# ver3.net
KiCad netlist of a schematic drawn in EAGLE
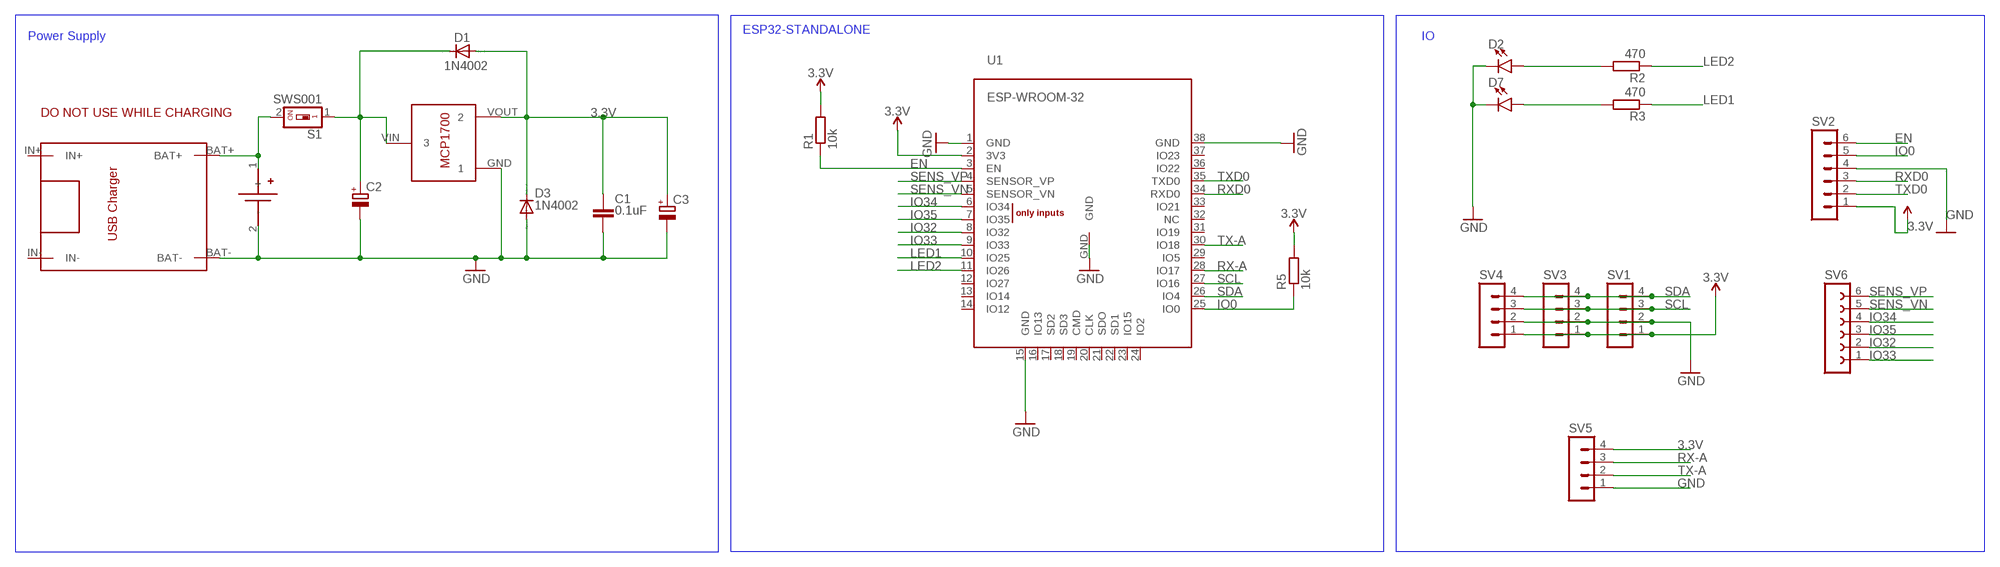
[diagram p0: schematic, sheet 1]

(export (version "E")
  (design (tool "Eeschema 10.0.6"))
  (components
    (comp (ref "C1")
      (value "0.1uF")
      (footprint "eagle-import:C075-052X106")
      (libsource (lib "eagle-import") (part "C-EU075-052X106"))
    )
    (comp (ref "C2")
      (value "CPOL-EU085CS-1AR")
      (footprint "eagle-import:085CS_1AR")
      (libsource (lib "eagle-import") (part "CPOL-EU085CS-1AR"))
    )
    (comp (ref "C3")
      (value "CPOL-EU085CS-1AR")
      (footprint "eagle-import:085CS_1AR")
      (libsource (lib "eagle-import") (part "CPOL-EU085CS-1AR"))
    )
    (comp (ref "D1")
      (value "1N4002")
      (footprint "eagle-import:DO41-10")
      (libsource (lib "eagle-import") (part "1N4004"))
    )
    (comp (ref "D2")
      (value "LED-3MM-NO_SILK")
      (footprint "eagle-import:LED_3MM-NS")
      (libsource (lib "eagle-import") (part "LED-3MM-NO_SILK"))
    )
    (comp (ref "D3")
      (value "1N4002")
      (footprint "eagle-import:DO41-10")
      (libsource (lib "eagle-import") (part "1N4004"))
    )
    (comp (ref "D7")
      (value "LED-3MM-NO_SILK")
      (footprint "eagle-import:LED_3MM-NS")
      (libsource (lib "eagle-import") (part "LED-3MM-NO_SILK"))
    )
    (comp (ref "R1")
      (value "10k")
      (footprint "eagle-import:R0603")
      (libsource (lib "eagle-import") (part "R-EU_R0603"))
    )
    (comp (ref "R2")
      (value "470")
      (footprint "eagle-import:R0603")
      (libsource (lib "eagle-import") (part "R-EU_R0603"))
    )
    (comp (ref "R3")
      (value "470")
      (footprint "eagle-import:R0603")
      (libsource (lib "eagle-import") (part "R-EU_R0603"))
    )
    (comp (ref "R5")
      (value "10k")
      (footprint "eagle-import:R0603")
      (libsource (lib "eagle-import") (part "R-EU_R0603"))
    )
    (comp (ref "S1")
      (value "SWS001")
      (footprint "eagle-import:SMS-001")
      (libsource (lib "eagle-import") (part "SWS001"))
    )
    (comp (ref "SV1")
      (value "MA04-1")
      (footprint "eagle-import:MA04-1")
      (libsource (lib "eagle-import") (part "MA04-1"))
    )
    (comp (ref "SV2")
      (value "MA06-1")
      (footprint "eagle-import:MA06-1")
      (libsource (lib "eagle-import") (part "MA06-1"))
    )
    (comp (ref "SV3")
      (value "MA04-1")
      (footprint "eagle-import:MA04-1")
      (libsource (lib "eagle-import") (part "MA04-1"))
    )
    (comp (ref "SV4")
      (value "MA04-1")
      (footprint "eagle-import:MA04-1")
      (libsource (lib "eagle-import") (part "MA04-1"))
    )
    (comp (ref "SV5")
      (value "MA04-1")
      (footprint "eagle-import:MA04-1")
      (libsource (lib "eagle-import") (part "MA04-1"))
    )
    (comp (ref "SV6")
      (value "FE06-1")
      (footprint "eagle-import:FE06")
      (libsource (lib "eagle-import") (part "FE06-1"))
    )
    (comp (ref "U$1")
      (value "BLOSSOM-BLM-18650-1PCS")
      (footprint "eagle-import:BLOSSOM-BLM-18650-1PCS")
      (libsource (lib "eagle-import") (part "BLOSSOM-BLM-18650-1PCS"))
    )
    (comp (ref "U$2")
      (value "TP4056")
      (footprint "eagle-import:TP4056")
      (libsource (lib "eagle-import") (part "TP4056"))
    )
    (comp (ref "U$3")
      (value "MCP1700T-3302E/TT")
      (footprint "eagle-import:MCP1700T-3302E_TT")
      (libsource (lib "eagle-import") (part "MCP1700T-3302E/TT"))
    )
    (comp (ref "U1")
      (value "ESP-WROOM-32")
      (footprint "eagle-import:ESP-WROOM-32")
      (libsource (lib "eagle-import") (part "ESP-WROOM-32"))
    )
  )
  (nets
    (net (code "1") (name "/EN") (class "Default")
      (node (ref "R1") (pin "1") (pinfunction "1_1") (pintype "passive"))
      (node (ref "SV2") (pin "6") (pinfunction "6_6") (pintype "passive"))
      (node (ref "U1") (pin "3") (pinfunction "EN_3") (pintype "bidirectional"))
    )
    (net (code "2") (name "/IO0") (class "Default")
      (node (ref "R5") (pin "1") (pinfunction "1_1") (pintype "passive"))
      (node (ref "SV2") (pin "5") (pinfunction "5_5") (pintype "passive"))
      (node (ref "U1") (pin "25") (pinfunction "IO0_25") (pintype "bidirectional"))
    )
    (net (code "3") (name "/IO32") (class "Default")
      (node (ref "SV6") (pin "2") (pinfunction "2_2") (pintype "passive"))
      (node (ref "U1") (pin "8") (pinfunction "IO32_8") (pintype "bidirectional"))
    )
    (net (code "4") (name "/IO33") (class "Default")
      (node (ref "SV6") (pin "1") (pinfunction "1_1") (pintype "passive"))
      (node (ref "U1") (pin "9") (pinfunction "IO33_9") (pintype "bidirectional"))
    )
    (net (code "5") (name "/IO34") (class "Default")
      (node (ref "SV6") (pin "4") (pinfunction "4_4") (pintype "passive"))
      (node (ref "U1") (pin "6") (pinfunction "IO34_6") (pintype "input"))
    )
    (net (code "6") (name "/IO35") (class "Default")
      (node (ref "SV6") (pin "3") (pinfunction "3_3") (pintype "passive"))
      (node (ref "U1") (pin "7") (pinfunction "IO35_7") (pintype "input"))
    )
    (net (code "7") (name "/LED1") (class "Default")
      (node (ref "R3") (pin "1") (pinfunction "1_1") (pintype "passive"))
      (node (ref "U1") (pin "10") (pinfunction "IO25_10") (pintype "bidirectional"))
    )
    (net (code "8") (name "/LED2") (class "Default")
      (node (ref "R2") (pin "1") (pinfunction "1_1") (pintype "passive"))
      (node (ref "U1") (pin "11") (pinfunction "IO26_11") (pintype "bidirectional"))
    )
    (net (code "9") (name "/RX-A") (class "Default")
      (node (ref "SV5") (pin "3") (pinfunction "3_3") (pintype "passive"))
      (node (ref "U1") (pin "28") (pinfunction "IO17_28") (pintype "bidirectional"))
    )
    (net (code "10") (name "/RXD0") (class "Default")
      (node (ref "SV2") (pin "3") (pinfunction "3_3") (pintype "passive"))
      (node (ref "U1") (pin "34") (pinfunction "RXD0_34") (pintype "bidirectional"))
    )
    (net (code "11") (name "/SCL") (class "Default")
      (node (ref "SV1") (pin "3") (pinfunction "3_3") (pintype "passive"))
      (node (ref "SV3") (pin "3") (pinfunction "3_3") (pintype "passive"))
      (node (ref "SV4") (pin "3") (pinfunction "3_3") (pintype "passive"))
      (node (ref "U1") (pin "27") (pinfunction "IO16_27") (pintype "bidirectional"))
    )
    (net (code "12") (name "/SDA") (class "Default")
      (node (ref "SV1") (pin "4") (pinfunction "4_4") (pintype "passive"))
      (node (ref "SV3") (pin "4") (pinfunction "4_4") (pintype "passive"))
      (node (ref "SV4") (pin "4") (pinfunction "4_4") (pintype "passive"))
      (node (ref "U1") (pin "26") (pinfunction "IO4_26") (pintype "bidirectional"))
    )
    (net (code "13") (name "/SENS_VN") (class "Default")
      (node (ref "SV6") (pin "5") (pinfunction "5_5") (pintype "passive"))
      (node (ref "U1") (pin "5") (pinfunction "SENSOR_VN_5") (pintype "input"))
    )
    (net (code "14") (name "/SENS_VP") (class "Default")
      (node (ref "SV6") (pin "6") (pinfunction "6_6") (pintype "passive"))
      (node (ref "U1") (pin "4") (pinfunction "SENSOR_VP_4") (pintype "input"))
    )
    (net (code "15") (name "/TX-A") (class "Default")
      (node (ref "SV5") (pin "2") (pinfunction "2_2") (pintype "passive"))
      (node (ref "U1") (pin "30") (pinfunction "IO18_30") (pintype "bidirectional"))
    )
    (net (code "16") (name "/TXD0") (class "Default")
      (node (ref "SV2") (pin "2") (pinfunction "2_2") (pintype "passive"))
      (node (ref "U1") (pin "35") (pinfunction "TXD0_35") (pintype "bidirectional"))
    )
    (net (code "17") (name "3.3V") (class "Default")
      (node (ref "C1") (pin "1") (pinfunction "1_1") (pintype "passive"))
      (node (ref "C3") (pin "+") (pinfunction "+_+") (pintype "passive"))
      (node (ref "D1") (pin "A") (pinfunction "A_A") (pintype "passive"))
      (node (ref "D3") (pin "C") (pinfunction "C_C") (pintype "passive"))
      (node (ref "R1") (pin "2") (pinfunction "2_2") (pintype "passive"))
      (node (ref "R5") (pin "2") (pinfunction "2_2") (pintype "passive"))
      (node (ref "SV1") (pin "1") (pinfunction "1_1") (pintype "passive"))
      (node (ref "SV2") (pin "1") (pinfunction "1_1") (pintype "passive"))
      (node (ref "SV3") (pin "1") (pinfunction "1_1") (pintype "passive"))
      (node (ref "SV4") (pin "1") (pinfunction "1_1") (pintype "passive"))
      (node (ref "SV5") (pin "4") (pinfunction "4_4") (pintype "passive"))
      (node (ref "U$3") (pin "VOUT") (pinfunction "2_VOUT") (pintype "bidirectional"))
      (node (ref "U1") (pin "2") (pinfunction "3V3_2") (pintype "bidirectional"))
    )
    (net (code "18") (name "GND") (class "Default")
      (node (ref "C1") (pin "2") (pinfunction "2_2") (pintype "passive"))
      (node (ref "C2") (pin "-") (pinfunction "-_-") (pintype "passive"))
      (node (ref "C3") (pin "-") (pinfunction "-_-") (pintype "passive"))
      (node (ref "D2") (pin "K") (pinfunction "C_K") (pintype "passive"))
      (node (ref "D3") (pin "A") (pinfunction "A_A") (pintype "passive"))
      (node (ref "D7") (pin "K") (pinfunction "C_K") (pintype "passive"))
      (node (ref "SV1") (pin "2") (pinfunction "2_2") (pintype "passive"))
      (node (ref "SV2") (pin "4") (pinfunction "4_4") (pintype "passive"))
      (node (ref "SV3") (pin "2") (pinfunction "2_2") (pintype "passive"))
      (node (ref "SV4") (pin "2") (pinfunction "2_2") (pintype "passive"))
      (node (ref "SV5") (pin "1") (pinfunction "1_1") (pintype "passive"))
      (node (ref "U$1") (pin "2") (pinfunction "-_2") (pintype "bidirectional"))
      (node (ref "U$2") (pin "BAT-") (pinfunction "BAT-_BAT-") (pintype "bidirectional"))
      (node (ref "U$3") (pin "GND") (pinfunction "1_GND") (pintype "bidirectional"))
      (node (ref "U1") (pin "1") (pinfunction "GND_1") (pintype "bidirectional"))
      (node (ref "U1") (pin "15") (pinfunction "GND_15") (pintype "bidirectional"))
      (node (ref "U1") (pin "38") (pinfunction "GND_38") (pintype "bidirectional"))
      (node (ref "U1") (pin "GND") (pinfunction "GND_GND") (pintype "bidirectional"))
    )
    (net (code "19") (name "Net-(D2-PadA)") (class "Default")
      (node (ref "D2") (pin "A") (pinfunction "A_A") (pintype "passive"))
      (node (ref "R2") (pin "2") (pinfunction "2_2") (pintype "passive"))
    )
    (net (code "20") (name "Net-(D7-PadA)") (class "Default")
      (node (ref "D7") (pin "A") (pinfunction "A_A") (pintype "passive"))
      (node (ref "R3") (pin "2") (pinfunction "2_2") (pintype "passive"))
    )
    (net (code "21") (name "Net-(U$1-+)") (class "Default")
      (node (ref "S1") (pin "2") (pinfunction "2_2") (pintype "passive"))
      (node (ref "U$1") (pin "1") (pinfunction "+_1") (pintype "bidirectional"))
      (node (ref "U$2") (pin "BAT+") (pinfunction "BAT+_BAT+") (pintype "bidirectional"))
    )
    (net (code "22") (name "Net-(U$3-3)") (class "Default")
      (node (ref "C2") (pin "+") (pinfunction "+_+") (pintype "passive"))
      (node (ref "D1") (pin "C") (pinfunction "C_C") (pintype "passive"))
      (node (ref "S1") (pin "1") (pinfunction "1_1") (pintype "passive"))
      (node (ref "U$3") (pin "VIN") (pinfunction "3_VIN") (pintype "bidirectional"))
    )
    (net (code "23") (name "unconnected-(U$2-PadIN+)") (class "Default")
      (node (ref "U$2") (pin "IN+") (pinfunction "IN+_IN+") (pintype "bidirectional"))
    )
    (net (code "24") (name "unconnected-(U$2-PadIN-)") (class "Default")
      (node (ref "U$2") (pin "IN-") (pinfunction "IN-_IN-") (pintype "bidirectional"))
    )
    (net (code "25") (name "unconnected-(U1-CLK-Pad20)") (class "Default")
      (node (ref "U1") (pin "20") (pinfunction "CLK_20") (pintype "bidirectional"))
    )
    (net (code "26") (name "unconnected-(U1-CMD-Pad19)") (class "Default")
      (node (ref "U1") (pin "19") (pinfunction "CMD_19") (pintype "bidirectional"))
    )
    (net (code "27") (name "unconnected-(U1-IO2-Pad24)") (class "Default")
      (node (ref "U1") (pin "24") (pinfunction "IO2_24") (pintype "bidirectional"))
    )
    (net (code "28") (name "unconnected-(U1-IO5-Pad29)") (class "Default")
      (node (ref "U1") (pin "29") (pinfunction "IO5_29") (pintype "bidirectional"))
    )
    (net (code "29") (name "unconnected-(U1-IO12-Pad14)") (class "Default")
      (node (ref "U1") (pin "14") (pinfunction "IO12_14") (pintype "bidirectional"))
    )
    (net (code "30") (name "unconnected-(U1-IO13-Pad16)") (class "Default")
      (node (ref "U1") (pin "16") (pinfunction "IO13_16") (pintype "bidirectional"))
    )
    (net (code "31") (name "unconnected-(U1-IO14-Pad13)") (class "Default")
      (node (ref "U1") (pin "13") (pinfunction "IO14_13") (pintype "bidirectional"))
    )
    (net (code "32") (name "unconnected-(U1-IO15-Pad23)") (class "Default")
      (node (ref "U1") (pin "23") (pinfunction "IO15_23") (pintype "bidirectional"))
    )
    (net (code "33") (name "unconnected-(U1-IO19-Pad31)") (class "Default")
      (node (ref "U1") (pin "31") (pinfunction "IO19_31") (pintype "bidirectional"))
    )
    (net (code "34") (name "unconnected-(U1-IO21-Pad33)") (class "Default")
      (node (ref "U1") (pin "33") (pinfunction "IO21_33") (pintype "bidirectional"))
    )
    (net (code "35") (name "unconnected-(U1-IO22-Pad36)") (class "Default")
      (node (ref "U1") (pin "36") (pinfunction "IO22_36") (pintype "bidirectional"))
    )
    (net (code "36") (name "unconnected-(U1-IO23-Pad37)") (class "Default")
      (node (ref "U1") (pin "37") (pinfunction "IO23_37") (pintype "bidirectional"))
    )
    (net (code "37") (name "unconnected-(U1-IO27-Pad12)") (class "Default")
      (node (ref "U1") (pin "12") (pinfunction "IO27_12") (pintype "bidirectional"))
    )
    (net (code "38") (name "unconnected-(U1-NC-Pad32)") (class "Default")
      (node (ref "U1") (pin "32") (pinfunction "NC_32") (pintype "bidirectional"))
    )
    (net (code "39") (name "unconnected-(U1-SD1-Pad22)") (class "Default")
      (node (ref "U1") (pin "22") (pinfunction "SD1_22") (pintype "bidirectional"))
    )
    (net (code "40") (name "unconnected-(U1-SD2-Pad17)") (class "Default")
      (node (ref "U1") (pin "17") (pinfunction "SD2_17") (pintype "bidirectional"))
    )
    (net (code "41") (name "unconnected-(U1-SD3-Pad18)") (class "Default")
      (node (ref "U1") (pin "18") (pinfunction "SD3_18") (pintype "bidirectional"))
    )
    (net (code "42") (name "unconnected-(U1-SDO-Pad21)") (class "Default")
      (node (ref "U1") (pin "21") (pinfunction "SDO_21") (pintype "bidirectional"))
    )
  )
)
